# Garten.net
KiCad netlist of a schematic drawn in EAGLE
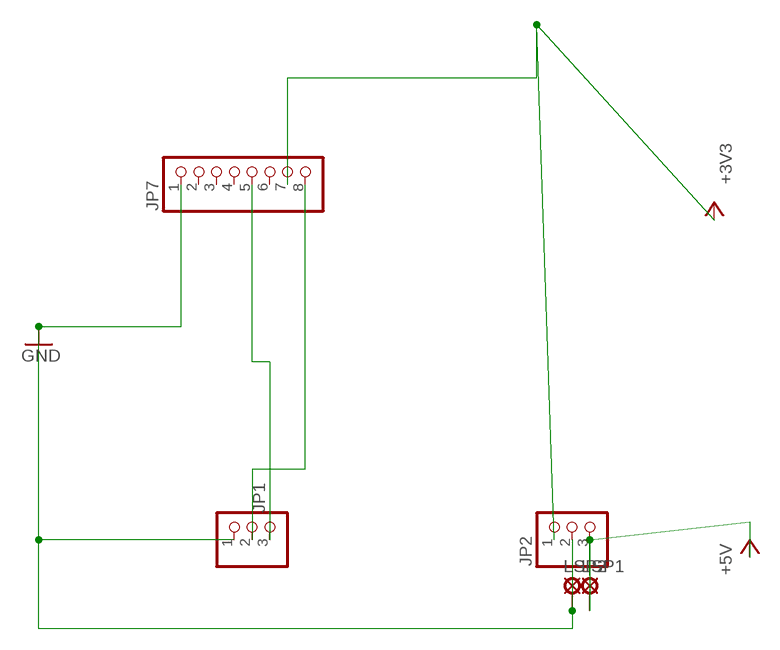
[diagram p0: schematic, sheet 1]

(export (version "E")
  (design (tool "Eeschema 10.0.6"))
  (components
    (comp (ref "JP1")
      (value "PINHD-1X3/90")
      (footprint "eagle-import:1X03_90")
      (libsource (lib "eagle-import") (part "PINHD-1X3/90"))
    )
    (comp (ref "JP2")
      (value "PINHD-1X3/90")
      (footprint "eagle-import:1X03_90")
      (libsource (lib "eagle-import") (part "PINHD-1X3/90"))
    )
    (comp (ref "JP7")
      (value "PINHD-1X8")
      (footprint "eagle-import:1X08")
      (libsource (lib "eagle-import") (part "PINHD-1X8"))
    )
    (comp (ref "LSP1")
      (value "SE11")
      (footprint "eagle-import:SE11")
      (libsource (lib "eagle-import") (part "SE11"))
    )
    (comp (ref "LSP2")
      (value "SE11")
      (footprint "eagle-import:SE11")
      (libsource (lib "eagle-import") (part "SE11"))
    )
  )
  (nets
    (net (code "1") (name "+3V3") (class "Default")
      (node (ref "JP2") (pin "1") (pinfunction "1_1") (pintype "passive"))
      (node (ref "JP7") (pin "7") (pinfunction "7_7") (pintype "passive"))
    )
    (net (code "2") (name "+5V") (class "Default")
      (node (ref "JP2") (pin "3") (pinfunction "3_3") (pintype "passive"))
      (node (ref "LSP1") (pin "MP") (pinfunction "MP_MP") (pintype "passive"))
    )
    (net (code "3") (name "GND") (class "Default")
      (node (ref "JP1") (pin "1") (pinfunction "1_1") (pintype "passive"))
      (node (ref "JP2") (pin "2") (pinfunction "2_2") (pintype "passive"))
      (node (ref "JP7") (pin "1") (pinfunction "1_1") (pintype "passive"))
      (node (ref "LSP2") (pin "MP") (pinfunction "MP_MP") (pintype "passive"))
    )
    (net (code "4") (name "Net-(JP1-Pad2)") (class "Default")
      (node (ref "JP1") (pin "2") (pinfunction "2_2") (pintype "passive"))
      (node (ref "JP7") (pin "8") (pinfunction "8_8") (pintype "passive"))
    )
    (net (code "5") (name "Net-(JP1-Pad3)") (class "Default")
      (node (ref "JP1") (pin "3") (pinfunction "3_3") (pintype "passive"))
      (node (ref "JP7") (pin "5") (pinfunction "5_5") (pintype "passive"))
    )
    (net (code "6") (name "unconnected-(JP7-Pad2)") (class "Default")
      (node (ref "JP7") (pin "2") (pinfunction "2_2") (pintype "passive"))
    )
    (net (code "7") (name "unconnected-(JP7-Pad3)") (class "Default")
      (node (ref "JP7") (pin "3") (pinfunction "3_3") (pintype "passive"))
    )
    (net (code "8") (name "unconnected-(JP7-Pad4)") (class "Default")
      (node (ref "JP7") (pin "4") (pinfunction "4_4") (pintype "passive"))
    )
    (net (code "9") (name "unconnected-(JP7-Pad6)") (class "Default")
      (node (ref "JP7") (pin "6") (pinfunction "6_6") (pintype "passive"))
    )
  )
)
